# LDO.net
KiCad netlist of a schematic drawn in Altium Designer
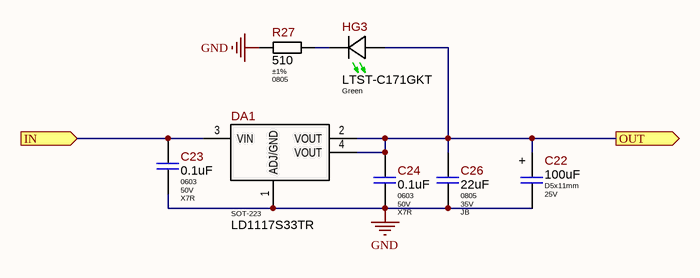
[diagram p0: LDO.SchDoc]

(export (version "E")
  (design (tool "Eeschema 10.0.6"))
  (components
    (comp (ref "C22")
      (value "100uF")
      (footprint "CAP-AE-PTH-50D05x110H15")
      (description "100uF 25V ±20% D5x11mm 105℃ Aluminum Electrolytic Capacitor")
      (fields
        (field (name "PACKAGE") "D5x11mm")
        (field (name "VOLTAGE") "25V")
        (field (name "PART NUMBER") "KRM-025V101MC110-T/A2")
        (field (name "MANUFACTURER") "Koshin")
      )
      (libsource (lib "capacitors") (part "KRM-025V101MC110-T/A2"))
    )
    (comp (ref "C23")
      (value "0.1uF")
      (footprint "C_CERAMIC_0603_MED")
      (description "100nF 50V X7R ±10% 0603 Ceramic Capacitor RoHS")
      (fields
        (field (name "PACKAGE") "0603")
        (field (name "VOLTAGE") "50V")
        (field (name "DIELECTRIC TYPE") "X7R")
        (field (name "PART NUMBER") "CL10B104KB8NNND")
        (field (name "MANUFACTURER") "Samsung Electro-Mechanics")
      )
      (libsource (lib "capacitors") (part "CL10B104KB8NNND"))
    )
    (comp (ref "C24")
      (value "0.1uF")
      (footprint "C_CERAMIC_0603_MED")
      (description "100nF 50V X7R ±10% 0603 Ceramic Capacitor RoHS")
      (fields
        (field (name "PACKAGE") "0603")
        (field (name "VOLTAGE") "50V")
        (field (name "DIELECTRIC TYPE") "X7R")
        (field (name "PART NUMBER") "CL10B104KB8NNND")
        (field (name "MANUFACTURER") "Samsung Electro-Mechanics")
      )
      (libsource (lib "capacitors") (part "CL10B104KB8NNND"))
    )
    (comp (ref "C26")
      (value "22uF")
      (footprint "CAP-0805(2012)X125T20")
      (description "22uF 35V JB ±20% 0805 Ceramic Capacitor RoHS")
      (fields
        (field (name "PACKAGE") "0805")
        (field (name "VOLTAGE") "35V")
        (field (name "DIELECTRIC TYPE") "JB")
        (field (name "PART NUMBER") "C2012JB1V226M125AC")
        (field (name "MANUFACTURER") "TDK Corporation")
      )
      (libsource (lib "capacitors") (part "C2012JB1V226M125AC"))
    )
    (comp (ref "DA1")
      (value "LD1117S33TR")
      (footprint "SOT-223")
      (description "Adjustable and fixed low drop positive voltage regulator, 3.3V 800mA, 1.25V to 15V Vin")
      (fields
        (field (name "PACKAGE") "SOT-223")
        (field (name "PART NUMBER") "LD1117S33TR")
        (field (name "MANUFACTURER") "STMicroelectronics")
      )
      (libsource (lib "ic") (part "LD1117S33TR"))
    )
    (comp (ref "HG3")
      (value "LTST-C171GKT")
      (footprint "LTST-C171GKT")
      (description "Low Power LED, Green 565nm, Clear, SMD 0805, Vf 2.1V - 2.6V, 5 ~ 12mcd @ 20 mA, 130°")
      (fields
        (field (name "PART NUMBER") "LTST-C171GKT")
        (field (name "COLOR") "Green")
        (field (name "MANUFACTURER") "Lite-On Optoelectronics")
      )
      (libsource (lib "opto") (part "LTST-C171GKT"))
    )
    (comp (ref "R27")
      (value "510")
      (footprint "R_ANY_CHIP_0805_MED")
      (description "510 Ohms ±1%, 1/2W 0805 High Power Thick Film Resistor")
      (fields
        (field (name "TOLERANCE") "±1%")
        (field (name "PACKAGE") "0805")
        (field (name "PART NUMBER") "ERJ-P06F5100V")
        (field (name "MANUFACTURER") "Panasonic")
      )
      (libsource (lib "resistors") (part "ERJ-P06F5100V"))
    )
  )
  (nets
    (net (code "1") (name "/IN") (class "Default")
      (node (ref "C23") (pin "2") (pinfunction "2_2") (pintype "passive"))
      (node (ref "DA1") (pin "3") (pinfunction "VIN_3") (pintype "passive"))
    )
    (net (code "2") (name "/OUT") (class "Default")
      (node (ref "C22") (pin "1") (pinfunction "1_1") (pintype "passive"))
      (node (ref "C24") (pin "2") (pinfunction "2_2") (pintype "passive"))
      (node (ref "C26") (pin "1") (pinfunction "1_1") (pintype "passive"))
      (node (ref "DA1") (pin "2") (pinfunction "VOUT_2") (pintype "passive"))
      (node (ref "DA1") (pin "4") (pinfunction "VOUT_4") (pintype "passive"))
      (node (ref "HG3") (pin "AN") (pinfunction "Anode_AN") (pintype "passive"))
    )
    (net (code "3") (name "GND") (class "Default")
      (node (ref "C22") (pin "2") (pinfunction "2_2") (pintype "passive"))
      (node (ref "C23") (pin "1") (pinfunction "1_1") (pintype "passive"))
      (node (ref "C24") (pin "1") (pinfunction "1_1") (pintype "passive"))
      (node (ref "C26") (pin "2") (pinfunction "2_2") (pintype "passive"))
      (node (ref "DA1") (pin "1") (pinfunction "ADJ/GND_1") (pintype "passive"))
      (node (ref "R27") (pin "2") (pintype "passive"))
    )
    (net (code "4") (name "Net-(HG3-Cathode)") (class "Default")
      (node (ref "HG3") (pin "CA") (pinfunction "Cathode_CA") (pintype "passive"))
      (node (ref "R27") (pin "1") (pintype "passive"))
    )
  )
)
